# Morpheus_IMU.net
KiCad netlist of a schematic drawn in Altium Designer
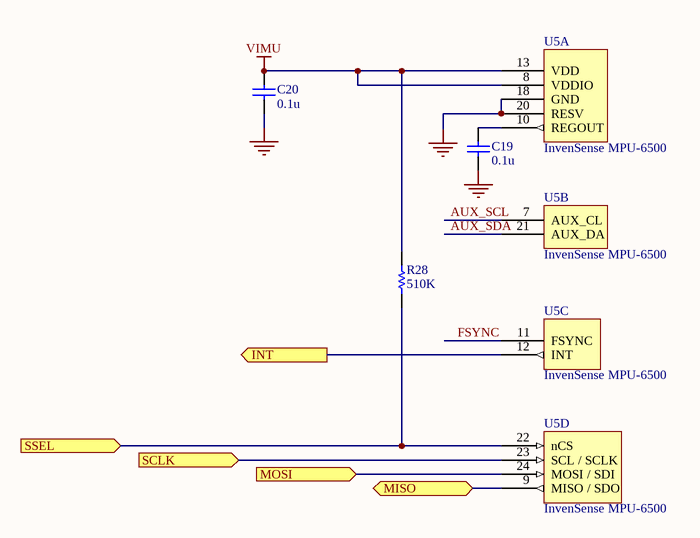
[diagram p0: Morpheus_IMU.SchDoc]

(export (version "E")
  (design (tool "Eeschema 10.0.6"))
  (components
    (comp (ref "C19")
      (value "0.1u")
      (footprint "CAP0402_SENSE_DVT")
      (description "Chip capacitor")
      (fields (field (name "TOLERANCE") "10%") (field (name "VOLTAGE") "50V"))
      (libsource (lib "Hello") (part "C_0.1u_10_50_X7R_0402"))
    )
    (comp (ref "C20")
      (value "0.1u")
      (footprint "CAP0402_SENSE_DVT")
      (description "Chip capacitor")
      (fields (field (name "TOLERANCE") "10%") (field (name "VOLTAGE") "50V"))
      (libsource (lib "Hello") (part "C_0.1u_10_50_X7R_0402"))
    )
    (comp (ref "R28")
      (value "510K")
      (footprint "RES0402_SENSE_DVT")
      (description "Chip Resistor")
      (fields (field (name "TOLERANCE") "5 %") (field (name "POWER") "0.1 W"))
      (libsource (lib "Hello") (part "R_510K_5_0.1_0402"))
    )
    (comp (ref "U5")
      (value "InvenSense MPU-6500")
      (footprint "QFN-24")
      (description "InvenSense MPU-6500 6-axis accelerometer and gyroscope")
      (libsource (lib "Hello") (part "MPU-6500"))
    )
  )
  (nets
    (net (code "1") (name "/AUX_SCL") (class "Default")
      (node (ref "U5") (pin "7") (pinfunction "AUX_CL_7") (pintype "passive"))
    )
    (net (code "2") (name "/AUX_SDA") (class "Default")
      (node (ref "U5") (pin "21") (pinfunction "AUX_DA_21") (pintype "passive"))
    )
    (net (code "3") (name "/FSYNC") (class "Default")
      (node (ref "U5") (pin "11") (pinfunction "FSYNC_11") (pintype "input"))
    )
    (net (code "4") (name "/INT") (class "Default")
      (node (ref "U5") (pin "12") (pinfunction "INT_12") (pintype "output"))
    )
    (net (code "5") (name "/MISO") (class "Default")
      (node (ref "U5") (pin "9") (pinfunction "MISO_/_SDO_9") (pintype "output"))
    )
    (net (code "6") (name "/MOSI") (class "Default")
      (node (ref "U5") (pin "24") (pinfunction "MOSI_/_SDI_24") (pintype "input"))
    )
    (net (code "7") (name "/SCLK") (class "Default")
      (node (ref "U5") (pin "23") (pinfunction "SCL_/_SCLK_23") (pintype "input"))
    )
    (net (code "8") (name "/SSEL") (class "Default")
      (node (ref "R28") (pin "1") (pinfunction "1_1") (pintype "passive"))
      (node (ref "U5") (pin "22") (pinfunction "nCS_22") (pintype "input"))
    )
    (net (code "9") (name "GND") (class "Default")
      (node (ref "C19") (pin "1") (pinfunction "1_1") (pintype "passive"))
      (node (ref "C20") (pin "1") (pinfunction "1_1") (pintype "passive"))
      (node (ref "U5") (pin "18") (pinfunction "GND_18") (pintype "power_in"))
      (node (ref "U5") (pin "20") (pinfunction "RESV_20") (pintype "passive"))
    )
    (net (code "10") (name "Net-(U5A-REGOUT)") (class "Default")
      (node (ref "C19") (pin "2") (pinfunction "2_2") (pintype "passive"))
      (node (ref "U5") (pin "10") (pinfunction "REGOUT_10") (pintype "output"))
    )
    (net (code "11") (name "VIMU") (class "Default")
      (node (ref "C20") (pin "2") (pinfunction "2_2") (pintype "passive"))
      (node (ref "R28") (pin "2") (pinfunction "2_2") (pintype "passive"))
      (node (ref "U5") (pin "13") (pinfunction "VDD_13") (pintype "power_in"))
      (node (ref "U5") (pin "8") (pinfunction "VDDIO_8") (pintype "power_in"))
    )
  )
)
